# ESP8266_V1_0.net
KiCad netlist of a schematic drawn in Altium Designer
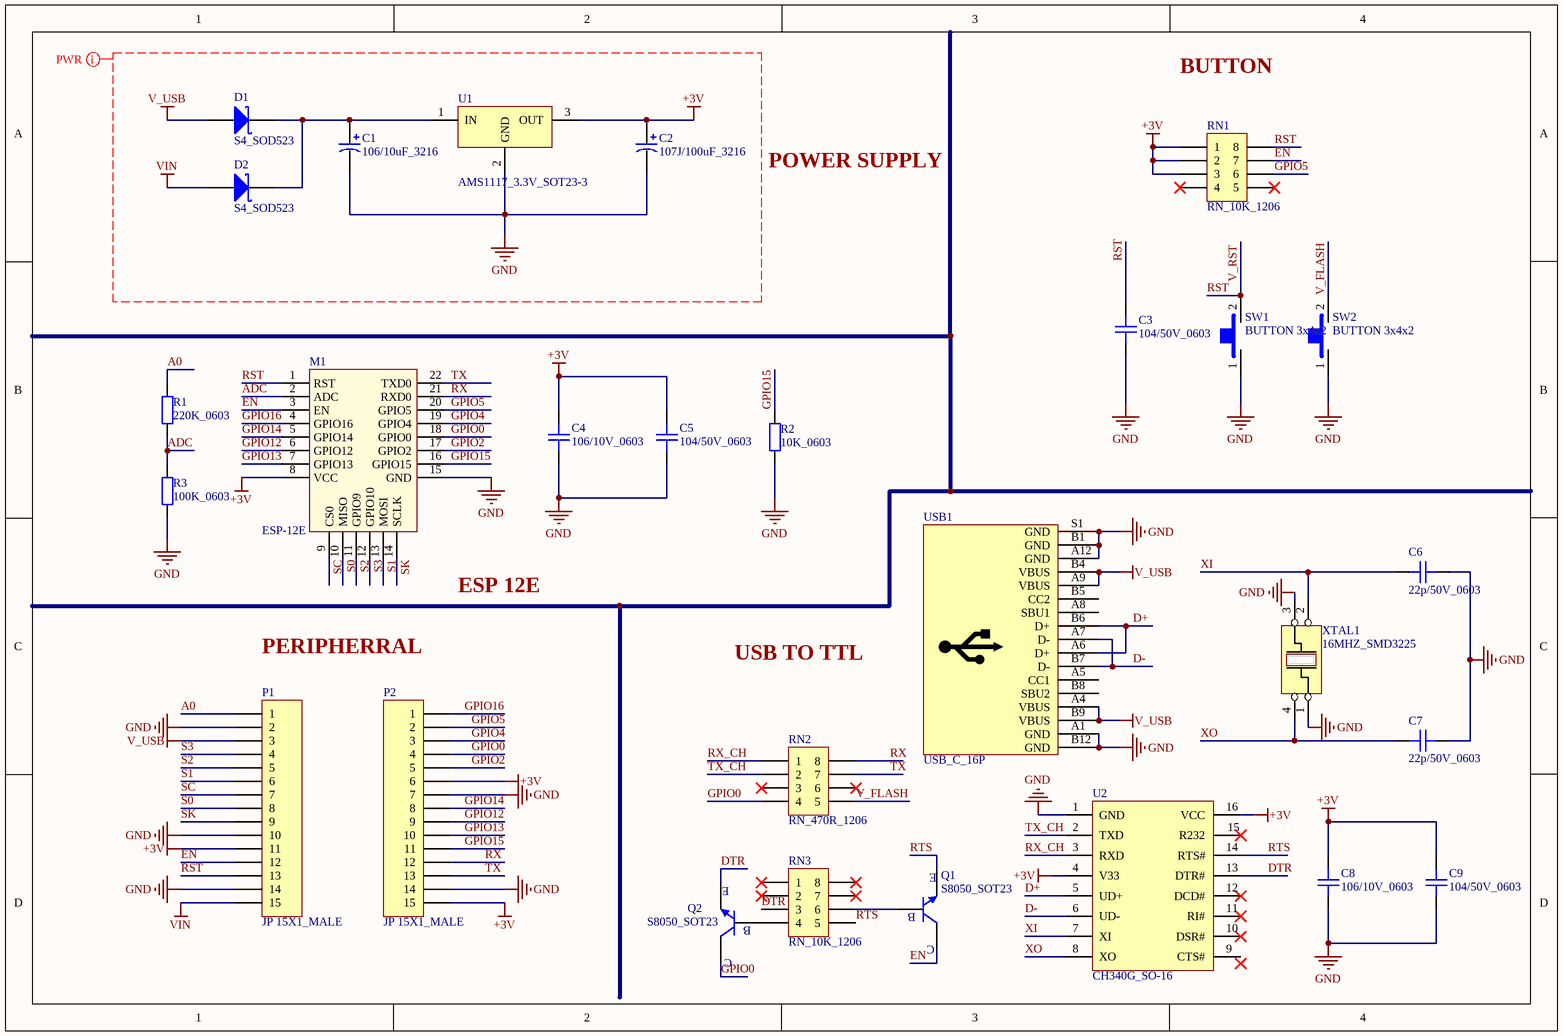
[diagram p0: ESP8266_V1.0.SchDoc]

(export (version "E")
  (design (tool "Eeschema 10.0.6"))
  (components
    (comp (ref "C1")
      (value "106/10uF_3216")
      (footprint "RESC TANTALUM- 1206 (3216)")
      (description "TAN_3216_106C _10UF_16V")
      (libsource (lib "01.Passive") (part "TANTALUM_3216_106C"))
    )
    (comp (ref "C2")
      (value "107J/100uF_3216")
      (footprint "RESC TANTALUM- 1206 (3216)")
      (description "TAN_3216_107J _100UF_16V")
      (libsource (lib "01.Passive") (part "TANTALUM_3216_107J"))
    )
    (comp (ref "C3")
      (value "104/50V_0603")
      (footprint "CAP - 0603 (1608)")
      (description "CAP CER 0.1uF 50V 10% X7R 0603")
      (fields (field (name "MPN") "C0603C104K5RACTU"))
      (libsource (lib "01.Passive") (part "C0603C104K5RACTU"))
    )
    (comp (ref "C4")
      (value "106/10V_0603")
      (footprint "CAP - 0603 (1608)")
      (description "CAP CER 10uF 10% 10V X5R 0603")
      (fields (field (name "MPN") "CL10A106KP8NNNC"))
      (libsource (lib "01.Passive") (part "CL10A106KP8NNNC"))
    )
    (comp (ref "C5")
      (value "104/50V_0603")
      (footprint "CAP - 0603 (1608)")
      (description "CAP CER 0.1uF 50V 10% X7R 0603")
      (fields (field (name "MPN") "C0603C104K5RACTU"))
      (libsource (lib "01.Passive") (part "C0603C104K5RACTU"))
    )
    (comp (ref "C6")
      (value "22p/50V_0603")
      (footprint "CAP - 0603 (1608)")
      (description "CAP CER 22pF 5% 50V C0G/NP0 0603")
      (fields (field (name "MPN") "CL10C200JB8NNNC"))
      (libsource (lib "01.Passive") (part "CL10C220JB8NNNC"))
    )
    (comp (ref "C7")
      (value "22p/50V_0603")
      (footprint "CAP - 0603 (1608)")
      (description "CAP CER 22pF 5% 50V C0G/NP0 0603")
      (fields (field (name "MPN") "CL10C200JB8NNNC"))
      (libsource (lib "01.Passive") (part "CL10C220JB8NNNC"))
    )
    (comp (ref "C8")
      (value "106/10V_0603")
      (footprint "CAP - 0603 (1608)")
      (description "CAP CER 10uF 10% 10V X5R 0603")
      (fields (field (name "MPN") "CL10A106KP8NNNC"))
      (libsource (lib "01.Passive") (part "CL10A106KP8NNNC"))
    )
    (comp (ref "C9")
      (value "104/50V_0603")
      (footprint "CAP - 0603 (1608)")
      (description "CAP CER 0.1uF 50V 10% X7R 0603")
      (fields (field (name "MPN") "C0603C104K5RACTU"))
      (libsource (lib "01.Passive") (part "C0603C104K5RACTU"))
    )
    (comp (ref "D1")
      (value "S4_SOD523")
      (footprint "SOD 523")
      (description "1N5819HW_S4_SOD523_DIODE SCHOTTKY_1A 40V")
      (libsource (lib "07. Power-Component") (part "1N5819HW_S4_SOD523"))
    )
    (comp (ref "D2")
      (value "S4_SOD523")
      (footprint "SOD 523")
      (description "1N5819HW_S4_SOD523_DIODE SCHOTTKY_1A 40V")
      (libsource (lib "07. Power-Component") (part "1N5819HW_S4_SOD523"))
    )
    (comp (ref "M1")
      (value "ESP-12E")
      (footprint "ESP-12E&F Module")
      (description "ESP-12E Module")
      (fields (field (name "MFR") "Espressif"))
      (libsource (lib "03.IC") (part "ESP-12E"))
    )
    (comp (ref "P1")
      (value "JP 15X1_MALE")
      (footprint "JP 2.54 15P")
      (description "JUMP_MALE_15 Pin Pitch 2.54mm")
      (fields (field (name "MPN") "S1012EC-40-ND"))
      (libsource (lib "") (part "JP 15x1_1"))
    )
    (comp (ref "P2")
      (value "JP 15X1_MALE")
      (footprint "JP 2.54 15P")
      (description "JUMP_MALE_15 Pin Pitch 2.54mm")
      (fields (field (name "MPN") "S1012EC-40-ND"))
      (libsource (lib "02.Connector-Header") (part "JP 15x1"))
    )
    (comp (ref "Q1")
      (value "S8050_SOT23")
      (footprint "SOT23- C1815")
      (description "TRANS_NPN_0.5A_SOT23-3")
      (libsource (lib "06.BJT") (part "S8050"))
    )
    (comp (ref "Q2")
      (value "S8050_SOT23")
      (footprint "SOT23- C1815")
      (description "TRANS_NPN_0.5A_SOT23-3")
      (libsource (lib "06.BJT") (part "S8050"))
    )
    (comp (ref "R1")
      (value "220K_0603")
      (footprint "RESC - 0603 (1806)")
      (description "RES SMD 220K OHM 1% 1/10W 0603")
      (fields (field (name "MPN") "RC0603FR-07220KL"))
      (libsource (lib "01.Passive") (part "RC0603FR-07220KL"))
    )
    (comp (ref "R2")
      (value "10K_0603")
      (footprint "RESC - 0603 (1806)")
      (description "RES SMD 10K OHM 1% 1/10W 0603")
      (fields (field (name "MPN") "RC0603FR-0710KL"))
      (libsource (lib "01.Passive") (part "RC0603FR-0710KL"))
    )
    (comp (ref "R3")
      (value "100K_0603")
      (footprint "RESC - 0603 (1806)")
      (description "RES SMD 100K OHM 1% 1/10W 0603")
      (fields (field (name "MPN") "RC0603FR-07100KL"))
      (libsource (lib "01.Passive") (part "RC0603FR-07100KL"))
    )
    (comp (ref "RN1")
      (value "RN_10K_1206")
      (footprint "RES ARRAY 1206")
      (description "CHIP ARRAY RESISTOR 10K 1206")
      (libsource (lib "01.Passive") (part "CHIP ARRAY RESISTOR 10K 1206"))
    )
    (comp (ref "RN2")
      (value "RN_470R_1206")
      (footprint "RES ARRAY 1206")
      (description "CHIP ARRAY RESISTOR 470R 1206")
      (libsource (lib "01.Passive") (part "CHIP ARRAY RESISTOR"))
    )
    (comp (ref "RN3")
      (value "RN_10K_1206")
      (footprint "RES ARRAY 1206")
      (description "CHIP ARRAY RESISTOR 10K 1206")
      (libsource (lib "01.Passive") (part "CHIP ARRAY RESISTOR 10K 1206"))
    )
    (comp (ref "SW1")
      (value "BUTTON 3x4x2")
      (footprint "BUTTON 3x4x2")
      (libsource (lib "02.Connector-Header") (part "BUTTON 3x4x2"))
    )
    (comp (ref "SW2")
      (value "BUTTON 3x4x2")
      (footprint "BUTTON 3x4x2")
      (libsource (lib "02.Connector-Header") (part "BUTTON 3x4x2"))
    )
    (comp (ref "U1")
      (value "AMS1117_3.3V_SOT23-3")
      (footprint "SOT 233")
      (libsource (lib "03.IC") (part "AMS1117-3.3"))
    )
    (comp (ref "U2")
      (value "CH340G_SO-16")
      (footprint "SO-16")
      (description "USB<->UART")
      (libsource (lib "03.IC") (part "CH340G"))
    )
    (comp (ref "USB1")
      (value "USB_C_16P")
      (footprint "USC16P")
      (fields (field (name "MF") "Valcon") (field (name "MP") "CSP-USC16-TR"))
      (libsource (lib "02.Connector-Header") (part "USB_C_16P"))
    )
    (comp (ref "XTAL1")
      (value "16MHZ_SMD3225")
      (footprint "CRYSTALL_SMD_3225")
      (description "CRYSTAL 16MHZ_SMD3225")
      (fields (field (name "MPN") "ABM8G-25.000MHZ-18-D2Y-T") (field (name "MFR") "Abracon LLC"))
      (libsource (lib "01.Passive") (part "16MHZ"))
    )
  )
  (nets
    (net (code "1") (name "+3V") (class "Default")
      (node (ref "C2") (pin "1") (pinfunction "1_1") (pintype "passive"))
      (node (ref "C4") (pin "2") (pinfunction "2_2") (pintype "passive"))
      (node (ref "C5") (pin "2") (pinfunction "2_2") (pintype "passive"))
      (node (ref "C8") (pin "2") (pinfunction "2_2") (pintype "passive"))
      (node (ref "C9") (pin "2") (pinfunction "2_2") (pintype "passive"))
      (node (ref "M1") (pin "8") (pinfunction "VCC_8") (pintype "passive"))
      (node (ref "P1") (pin "11") (pinfunction "11_11") (pintype "passive"))
      (node (ref "P2") (pin "15") (pinfunction "15_15") (pintype "passive"))
      (node (ref "P2") (pin "6") (pinfunction "6_6") (pintype "passive"))
      (node (ref "RN1") (pin "1") (pinfunction "1_1") (pintype "passive"))
      (node (ref "RN1") (pin "2") (pinfunction "2_2") (pintype "passive"))
      (node (ref "RN1") (pin "3") (pinfunction "3_3") (pintype "passive"))
      (node (ref "U1") (pin "3") (pinfunction "OUT_3") (pintype "passive"))
      (node (ref "U2") (pin "16") (pinfunction "VCC_16") (pintype "passive"))
      (node (ref "U2") (pin "4") (pinfunction "V33_4") (pintype "power_in"))
    )
    (net (code "2") (name "/A0") (class "Default")
      (node (ref "P1") (pin "1") (pinfunction "1_1") (pintype "passive"))
      (node (ref "R1") (pin "2") (pinfunction "2_2") (pintype "passive"))
    )
    (net (code "3") (name "/ADC") (class "Default")
      (node (ref "M1") (pin "2") (pinfunction "ADC_2") (pintype "passive"))
      (node (ref "R1") (pin "1") (pinfunction "1_1") (pintype "passive"))
      (node (ref "R3") (pin "2") (pinfunction "2_2") (pintype "passive"))
    )
    (net (code "4") (name "/D+") (class "Default")
      (node (ref "U2") (pin "5") (pinfunction "UD+_5") (pintype "power_in"))
      (node (ref "USB1") (pin "A6") (pinfunction "D+_A6") (pintype "passive"))
      (node (ref "USB1") (pin "B6") (pinfunction "D+_B6") (pintype "passive"))
    )
    (net (code "5") (name "/D-") (class "Default")
      (node (ref "U2") (pin "6") (pinfunction "UD-_6") (pintype "power_in"))
      (node (ref "USB1") (pin "A7") (pinfunction "D-_A7") (pintype "passive"))
      (node (ref "USB1") (pin "B7") (pinfunction "D-_B7") (pintype "passive"))
    )
    (net (code "6") (name "/DTR") (class "Default")
      (node (ref "Q2") (pin "2") (pinfunction "E_2") (pintype "passive"))
      (node (ref "RN3") (pin "3") (pinfunction "3_3") (pintype "passive"))
      (node (ref "U2") (pin "13") (pinfunction "DTR#_13") (pintype "passive"))
    )
    (net (code "7") (name "/EN") (class "Default")
      (node (ref "M1") (pin "3") (pinfunction "EN_3") (pintype "passive"))
      (node (ref "P1") (pin "12") (pinfunction "12_12") (pintype "passive"))
      (node (ref "Q1") (pin "3") (pinfunction "C_3") (pintype "passive"))
      (node (ref "RN1") (pin "7") (pinfunction "7_7") (pintype "passive"))
    )
    (net (code "8") (name "/GPIO0") (class "Default")
      (node (ref "M1") (pin "18") (pinfunction "GPIO0_18") (pintype "passive"))
      (node (ref "P2") (pin "4") (pinfunction "4_4") (pintype "passive"))
      (node (ref "Q2") (pin "3") (pinfunction "C_3") (pintype "passive"))
      (node (ref "RN2") (pin "4") (pinfunction "4_4") (pintype "passive"))
    )
    (net (code "9") (name "/GPIO2") (class "Default")
      (node (ref "M1") (pin "17") (pinfunction "GPIO2_17") (pintype "passive"))
      (node (ref "P2") (pin "5") (pinfunction "5_5") (pintype "passive"))
    )
    (net (code "10") (name "/GPIO4") (class "Default")
      (node (ref "M1") (pin "19") (pinfunction "GPIO4_19") (pintype "passive"))
      (node (ref "P2") (pin "3") (pinfunction "3_3") (pintype "passive"))
    )
    (net (code "11") (name "/GPIO5") (class "Default")
      (node (ref "M1") (pin "20") (pinfunction "GPIO5_20") (pintype "passive"))
      (node (ref "P2") (pin "2") (pinfunction "2_2") (pintype "passive"))
      (node (ref "RN1") (pin "6") (pinfunction "6_6") (pintype "passive"))
    )
    (net (code "12") (name "/GPIO12") (class "Default")
      (node (ref "M1") (pin "6") (pinfunction "GPIO12_6") (pintype "passive"))
      (node (ref "P2") (pin "9") (pinfunction "9_9") (pintype "passive"))
    )
    (net (code "13") (name "/GPIO13") (class "Default")
      (node (ref "M1") (pin "7") (pinfunction "GPIO13_7") (pintype "passive"))
      (node (ref "P2") (pin "10") (pinfunction "10_10") (pintype "passive"))
    )
    (net (code "14") (name "/GPIO14") (class "Default")
      (node (ref "M1") (pin "5") (pinfunction "GPIO14_5") (pintype "passive"))
      (node (ref "P2") (pin "8") (pinfunction "8_8") (pintype "passive"))
    )
    (net (code "15") (name "/GPIO15") (class "Default")
      (node (ref "M1") (pin "16") (pinfunction "GPIO15_16") (pintype "passive"))
      (node (ref "P2") (pin "11") (pinfunction "11_11") (pintype "passive"))
      (node (ref "R2") (pin "2") (pinfunction "2_2") (pintype "passive"))
    )
    (net (code "16") (name "/GPIO16") (class "Default")
      (node (ref "M1") (pin "4") (pinfunction "GPIO16_4") (pintype "passive"))
      (node (ref "P2") (pin "1") (pinfunction "1_1") (pintype "passive"))
    )
    (net (code "17") (name "/RST") (class "Default")
      (node (ref "C3") (pin "2") (pinfunction "2_2") (pintype "passive"))
      (node (ref "M1") (pin "1") (pinfunction "RST_1") (pintype "passive"))
      (node (ref "P1") (pin "13") (pinfunction "13_13") (pintype "passive"))
      (node (ref "RN1") (pin "8") (pinfunction "8_8") (pintype "passive"))
      (node (ref "SW1") (pin "2") (pinfunction "2_2") (pintype "passive"))
    )
    (net (code "18") (name "/RTS") (class "Default")
      (node (ref "Q1") (pin "2") (pinfunction "E_2") (pintype "passive"))
      (node (ref "RN3") (pin "5") (pinfunction "5_5") (pintype "passive"))
      (node (ref "U2") (pin "14") (pinfunction "RTS#_14") (pintype "passive"))
    )
    (net (code "19") (name "/RX") (class "Default")
      (node (ref "M1") (pin "21") (pinfunction "RXD0_21") (pintype "passive"))
      (node (ref "P2") (pin "12") (pinfunction "12_12") (pintype "passive"))
      (node (ref "RN2") (pin "8") (pinfunction "8_8") (pintype "passive"))
    )
    (net (code "20") (name "/RX_CH") (class "Default")
      (node (ref "RN2") (pin "1") (pinfunction "1_1") (pintype "passive"))
      (node (ref "U2") (pin "3") (pinfunction "RXD_3") (pintype "power_in"))
    )
    (net (code "21") (name "/S0") (class "Default")
      (node (ref "M1") (pin "10") (pinfunction "MISO_10") (pintype "passive"))
      (node (ref "P1") (pin "8") (pinfunction "8_8") (pintype "passive"))
    )
    (net (code "22") (name "/S1") (class "Default")
      (node (ref "M1") (pin "13") (pinfunction "MOSI_13") (pintype "passive"))
      (node (ref "P1") (pin "6") (pinfunction "6_6") (pintype "passive"))
    )
    (net (code "23") (name "/S2") (class "Default")
      (node (ref "M1") (pin "11") (pinfunction "GPIO9_11") (pintype "passive"))
      (node (ref "P1") (pin "5") (pinfunction "5_5") (pintype "passive"))
    )
    (net (code "24") (name "/S3") (class "Default")
      (node (ref "M1") (pin "12") (pinfunction "GPIO10_12") (pintype "passive"))
      (node (ref "P1") (pin "4") (pinfunction "4_4") (pintype "passive"))
    )
    (net (code "25") (name "/SC") (class "Default")
      (node (ref "M1") (pin "9") (pinfunction "CS0_9") (pintype "passive"))
      (node (ref "P1") (pin "7") (pinfunction "7_7") (pintype "passive"))
    )
    (net (code "26") (name "/SK") (class "Default")
      (node (ref "M1") (pin "14") (pinfunction "SCLK_14") (pintype "passive"))
      (node (ref "P1") (pin "9") (pinfunction "9_9") (pintype "passive"))
    )
    (net (code "27") (name "/TX") (class "Default")
      (node (ref "M1") (pin "22") (pinfunction "TXD0_22") (pintype "passive"))
      (node (ref "P2") (pin "13") (pinfunction "13_13") (pintype "passive"))
      (node (ref "RN2") (pin "7") (pinfunction "7_7") (pintype "passive"))
    )
    (net (code "28") (name "/TX_CH") (class "Default")
      (node (ref "RN2") (pin "2") (pinfunction "2_2") (pintype "passive"))
      (node (ref "U2") (pin "2") (pinfunction "TXD_2") (pintype "power_in"))
    )
    (net (code "29") (name "/V_FLASH") (class "Default")
      (node (ref "RN2") (pin "5") (pinfunction "5_5") (pintype "passive"))
      (node (ref "SW2") (pin "2") (pinfunction "2_2") (pintype "passive"))
    )
    (net (code "30") (name "/XI") (class "Default")
      (node (ref "C6") (pin "2") (pinfunction "2_2") (pintype "passive"))
      (node (ref "U2") (pin "7") (pinfunction "XI_7") (pintype "power_in"))
      (node (ref "XTAL1") (pin "2") (pinfunction "2_2") (pintype "passive"))
    )
    (net (code "31") (name "/XO") (class "Default")
      (node (ref "C7") (pin "2") (pinfunction "2_2") (pintype "passive"))
      (node (ref "U2") (pin "8") (pinfunction "XO_8") (pintype "power_in"))
      (node (ref "XTAL1") (pin "4") (pinfunction "4_4") (pintype "passive"))
    )
    (net (code "32") (name "GND") (class "Default")
      (node (ref "C1") (pin "2") (pinfunction "2_2") (pintype "passive"))
      (node (ref "C2") (pin "2") (pinfunction "2_2") (pintype "passive"))
      (node (ref "C3") (pin "1") (pinfunction "1_1") (pintype "passive"))
      (node (ref "C4") (pin "1") (pinfunction "1_1") (pintype "passive"))
      (node (ref "C5") (pin "1") (pinfunction "1_1") (pintype "passive"))
      (node (ref "C6") (pin "1") (pinfunction "1_1") (pintype "passive"))
      (node (ref "C7") (pin "1") (pinfunction "1_1") (pintype "passive"))
      (node (ref "C8") (pin "1") (pinfunction "1_1") (pintype "passive"))
      (node (ref "C9") (pin "1") (pinfunction "1_1") (pintype "passive"))
      (node (ref "M1") (pin "15") (pinfunction "GND_15") (pintype "passive"))
      (node (ref "P1") (pin "10") (pinfunction "10_10") (pintype "passive"))
      (node (ref "P1") (pin "14") (pinfunction "14_14") (pintype "passive"))
      (node (ref "P1") (pin "2") (pinfunction "2_2") (pintype "passive"))
      (node (ref "P2") (pin "14") (pinfunction "14_14") (pintype "passive"))
      (node (ref "P2") (pin "7") (pinfunction "7_7") (pintype "passive"))
      (node (ref "R2") (pin "1") (pinfunction "1_1") (pintype "passive"))
      (node (ref "R3") (pin "1") (pinfunction "1_1") (pintype "passive"))
      (node (ref "SW1") (pin "1") (pinfunction "1_1") (pintype "passive"))
      (node (ref "SW2") (pin "1") (pinfunction "1_1") (pintype "passive"))
      (node (ref "U1") (pin "2") (pinfunction "GND_2") (pintype "passive"))
      (node (ref "U2") (pin "1") (pinfunction "GND_1") (pintype "power_in"))
      (node (ref "USB1") (pin "A1") (pinfunction "GND_A1") (pintype "passive"))
      (node (ref "USB1") (pin "A12") (pinfunction "GND_A12") (pintype "passive"))
      (node (ref "USB1") (pin "B1") (pinfunction "GND_B1") (pintype "passive"))
      (node (ref "USB1") (pin "B12") (pinfunction "GND_B12") (pintype "passive"))
      (node (ref "USB1") (pin "S1") (pinfunction "GND_S1") (pintype "passive"))
      (node (ref "XTAL1") (pin "1") (pinfunction "1_1") (pintype "passive"))
      (node (ref "XTAL1") (pin "3") (pinfunction "3_3") (pintype "passive"))
    )
    (net (code "33") (name "Net-(D1-K)") (class "Default")
      (node (ref "C1") (pin "1") (pinfunction "1_1") (pintype "passive"))
      (node (ref "D1") (pin "2") (pinfunction "K_2") (pintype "passive"))
      (node (ref "D2") (pin "2") (pinfunction "K_2") (pintype "passive"))
      (node (ref "U1") (pin "1") (pinfunction "IN_1") (pintype "passive"))
    )
    (net (code "34") (name "Net-(Q1-B)") (class "Default")
      (node (ref "Q1") (pin "1") (pinfunction "B_1") (pintype "passive"))
      (node (ref "RN3") (pin "6") (pinfunction "6_6") (pintype "passive"))
    )
    (net (code "35") (name "Net-(Q2-B)") (class "Default")
      (node (ref "Q2") (pin "1") (pinfunction "B_1") (pintype "passive"))
      (node (ref "RN3") (pin "4") (pinfunction "4_4") (pintype "passive"))
    )
    (net (code "36") (name "VIN") (class "Default")
      (node (ref "D2") (pin "1") (pinfunction "A_1") (pintype "passive"))
      (node (ref "P1") (pin "15") (pinfunction "15_15") (pintype "passive"))
    )
    (net (code "37") (name "V_USB") (class "Default")
      (node (ref "D1") (pin "1") (pinfunction "A_1") (pintype "passive"))
      (node (ref "P1") (pin "3") (pinfunction "3_3") (pintype "passive"))
      (node (ref "USB1") (pin "A4") (pinfunction "VBUS_A4") (pintype "passive"))
      (node (ref "USB1") (pin "A9") (pinfunction "VBUS_A9") (pintype "passive"))
      (node (ref "USB1") (pin "B4") (pinfunction "VBUS_B4") (pintype "passive"))
      (node (ref "USB1") (pin "B9") (pinfunction "VBUS_B9") (pintype "passive"))
    )
    (net (code "38") (name "unconnected-(RN1-Pad4)") (class "Default")
      (node (ref "RN1") (pin "4") (pinfunction "4_4") (pintype "passive+no_connect"))
    )
    (net (code "39") (name "unconnected-(RN1-Pad5)") (class "Default")
      (node (ref "RN1") (pin "5") (pinfunction "5_5") (pintype "passive+no_connect"))
    )
    (net (code "40") (name "unconnected-(RN2-Pad3)") (class "Default")
      (node (ref "RN2") (pin "3") (pinfunction "3_3") (pintype "passive+no_connect"))
    )
    (net (code "41") (name "unconnected-(RN2-Pad6)") (class "Default")
      (node (ref "RN2") (pin "6") (pinfunction "6_6") (pintype "passive+no_connect"))
    )
    (net (code "42") (name "unconnected-(RN3-Pad1)") (class "Default")
      (node (ref "RN3") (pin "1") (pinfunction "1_1") (pintype "passive+no_connect"))
    )
    (net (code "43") (name "unconnected-(RN3-Pad2)") (class "Default")
      (node (ref "RN3") (pin "2") (pinfunction "2_2") (pintype "passive+no_connect"))
    )
    (net (code "44") (name "unconnected-(RN3-Pad7)") (class "Default")
      (node (ref "RN3") (pin "7") (pinfunction "7_7") (pintype "passive+no_connect"))
    )
    (net (code "45") (name "unconnected-(RN3-Pad8)") (class "Default")
      (node (ref "RN3") (pin "8") (pinfunction "8_8") (pintype "passive+no_connect"))
    )
    (net (code "46") (name "unconnected-(U2-CTS#-Pad9)") (class "Default")
      (node (ref "U2") (pin "9") (pinfunction "CTS#_9") (pintype "passive"))
    )
    (net (code "47") (name "unconnected-(U2-DCD#-Pad12)") (class "Default")
      (node (ref "U2") (pin "12") (pinfunction "DCD#_12") (pintype "passive+no_connect"))
    )
    (net (code "48") (name "unconnected-(U2-DSR#-Pad10)") (class "Default")
      (node (ref "U2") (pin "10") (pinfunction "DSR#_10") (pintype "passive+no_connect"))
    )
    (net (code "49") (name "unconnected-(U2-R232-Pad15)") (class "Default")
      (node (ref "U2") (pin "15") (pinfunction "R232_15") (pintype "passive+no_connect"))
    )
    (net (code "50") (name "unconnected-(U2-RI#-Pad11)") (class "Default")
      (node (ref "U2") (pin "11") (pinfunction "RI#_11") (pintype "passive+no_connect"))
    )
    (net (code "51") (name "unconnected-(USB1-CC1-PadA5)") (class "Default")
      (node (ref "USB1") (pin "A5") (pinfunction "CC1_A5") (pintype "passive"))
    )
    (net (code "52") (name "unconnected-(USB1-CC2-PadB5)") (class "Default")
      (node (ref "USB1") (pin "B5") (pinfunction "CC2_B5") (pintype "passive"))
    )
    (net (code "53") (name "unconnected-(USB1-SBU1-PadA8)") (class "Default")
      (node (ref "USB1") (pin "A8") (pinfunction "SBU1_A8") (pintype "passive"))
    )
    (net (code "54") (name "unconnected-(USB1-SBU2-PadB8)") (class "Default")
      (node (ref "USB1") (pin "B8") (pinfunction "SBU2_B8") (pintype "passive"))
    )
  )
)
